# Water_Monitor_Interface_v7.net
KiCad netlist of a schematic drawn in EAGLE
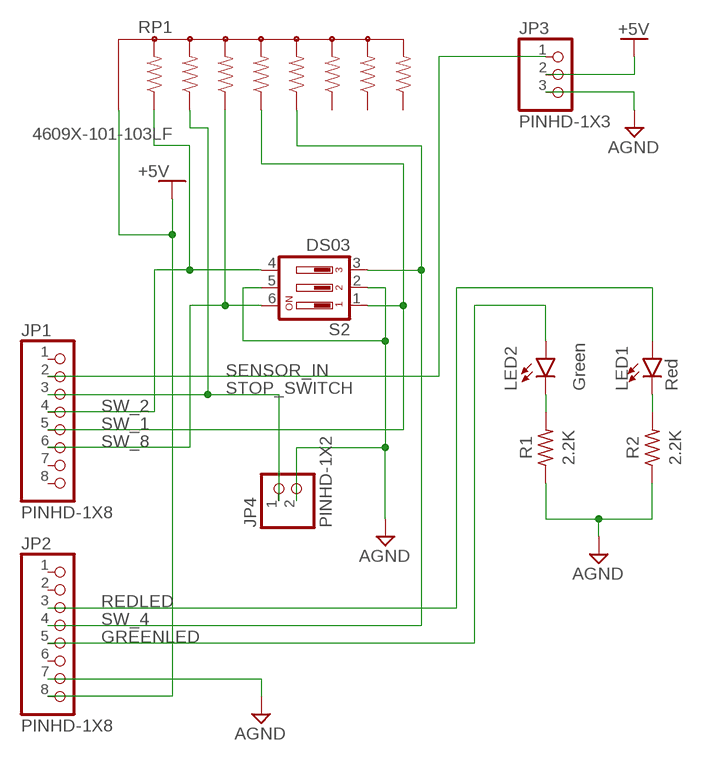
[diagram p0: schematic, sheet 1]

(export (version "E")
  (design (tool "Eeschema 10.0.6"))
  (components
    (comp (ref "JP1")
      (value "PINHD-1X8")
      (footprint "eagle-import:1X08")
      (libsource (lib "eagle-import") (part "PINHD-1X8"))
    )
    (comp (ref "JP2")
      (value "PINHD-1X8")
      (footprint "eagle-import:1X08")
      (libsource (lib "eagle-import") (part "PINHD-1X8"))
    )
    (comp (ref "JP3")
      (value "PINHD-1X3")
      (footprint "eagle-import:1X03")
      (libsource (lib "eagle-import") (part "PINHD-1X3"))
    )
    (comp (ref "JP4")
      (value "PINHD-1X2")
      (footprint "eagle-import:1X02")
      (libsource (lib "eagle-import") (part "PINHD-1X2"))
    )
    (comp (ref "LED1")
      (value "Red")
      (footprint "eagle-import:LED3MM")
      (libsource (lib "eagle-import") (part "led_259_LED3MM"))
    )
    (comp (ref "LED2")
      (value "Green")
      (footprint "eagle-import:LED_3MM-NS")
      (libsource (lib "eagle-import") (part "LED-3MM-NO_SILK"))
    )
    (comp (ref "R1")
      (value "2.2K")
      (footprint "eagle-import:RESAD724W46L381D178B")
      (libsource (lib "eagle-import") (part "R-USAXIAL-7.2MM-PITCH_"))
    )
    (comp (ref "R2")
      (value "2.2K")
      (footprint "eagle-import:RESAD724W46L381D178B")
      (libsource (lib "eagle-import") (part "R-USAXIAL-7.2MM-PITCH_"))
    )
    (comp (ref "RP1")
      (value "4609X-101-103LF")
      (footprint "eagle-import:4609X-101-103LF")
      (fields (field (name "MANUFACTURER") "Bourns Inc.") (field (name "CREATED_BY") "PCBLayout.com"))
      (libsource (lib "eagle-import") (part "4609X-101-103LF"))
    )
    (comp (ref "S2")
      (value "DS03")
      (footprint "eagle-import:DS-03")
      (fields (field (name "MPN") "MCNDS-03-V"))
      (libsource (lib "eagle-import") (part "DS03"))
    )
  )
  (nets
    (net (code "1") (name "+5V") (class "Default")
      (node (ref "JP2") (pin "8") (pinfunction "8_8") (pintype "passive"))
      (node (ref "JP3") (pin "2") (pinfunction "2_2") (pintype "passive"))
      (node (ref "RP1") (pin "1") (pinfunction "1_1") (pintype "passive"))
    )
    (net (code "2") (name "/GREENLED") (class "Default")
      (node (ref "JP2") (pin "5") (pinfunction "5_5") (pintype "passive"))
      (node (ref "LED2") (pin "A") (pinfunction "A_A") (pintype "passive"))
    )
    (net (code "3") (name "/REDLED") (class "Default")
      (node (ref "JP2") (pin "3") (pinfunction "3_3") (pintype "passive"))
      (node (ref "LED1") (pin "A") (pinfunction "A_A") (pintype "passive"))
    )
    (net (code "4") (name "/SENSOR_IN") (class "Default")
      (node (ref "JP1") (pin "2") (pinfunction "2_2") (pintype "passive"))
      (node (ref "JP3") (pin "1") (pinfunction "1_1") (pintype "passive"))
    )
    (net (code "5") (name "/STOP_SWITCH") (class "Default")
      (node (ref "JP1") (pin "3") (pinfunction "3_3") (pintype "passive"))
      (node (ref "JP4") (pin "1") (pinfunction "1_1") (pintype "passive"))
      (node (ref "RP1") (pin "3") (pinfunction "3_3") (pintype "passive"))
    )
    (net (code "6") (name "/SW_1") (class "Default")
      (node (ref "JP1") (pin "5") (pinfunction "5_5") (pintype "passive"))
      (node (ref "RP1") (pin "5") (pinfunction "5_5") (pintype "passive"))
      (node (ref "S2") (pin "1") (pinfunction "1_1") (pintype "passive"))
    )
    (net (code "7") (name "/SW_2") (class "Default")
      (node (ref "JP1") (pin "4") (pinfunction "4_4") (pintype "passive"))
      (node (ref "RP1") (pin "2") (pinfunction "2_2") (pintype "passive"))
      (node (ref "S2") (pin "4") (pinfunction "4_4") (pintype "passive"))
    )
    (net (code "8") (name "/SW_4") (class "Default")
      (node (ref "JP2") (pin "4") (pinfunction "4_4") (pintype "passive"))
      (node (ref "RP1") (pin "6") (pinfunction "6_6") (pintype "passive"))
      (node (ref "S2") (pin "3") (pinfunction "3_3") (pintype "passive"))
    )
    (net (code "9") (name "/SW_8") (class "Default")
      (node (ref "JP1") (pin "6") (pinfunction "6_6") (pintype "passive"))
      (node (ref "RP1") (pin "4") (pinfunction "4_4") (pintype "passive"))
      (node (ref "S2") (pin "6") (pinfunction "6_6") (pintype "passive"))
    )
    (net (code "10") (name "AGND") (class "Default")
      (node (ref "JP2") (pin "7") (pinfunction "7_7") (pintype "passive"))
      (node (ref "JP3") (pin "3") (pinfunction "3_3") (pintype "passive"))
      (node (ref "JP4") (pin "2") (pinfunction "2_2") (pintype "passive"))
      (node (ref "R1") (pin "1") (pinfunction "1_1") (pintype "passive"))
      (node (ref "R2") (pin "1") (pinfunction "1_1") (pintype "passive"))
      (node (ref "S2") (pin "2") (pinfunction "2_2") (pintype "passive"))
      (node (ref "S2") (pin "5") (pinfunction "5_5") (pintype "passive"))
    )
    (net (code "11") (name "Net-(LED1-C)") (class "Default")
      (node (ref "LED1") (pin "K") (pinfunction "C_K") (pintype "passive"))
      (node (ref "R2") (pin "2") (pinfunction "2_2") (pintype "passive"))
    )
    (net (code "12") (name "Net-(LED2-C)") (class "Default")
      (node (ref "LED2") (pin "K") (pinfunction "C_K") (pintype "passive"))
      (node (ref "R1") (pin "2") (pinfunction "2_2") (pintype "passive"))
    )
    (net (code "13") (name "unconnected-(JP1-Pad1)") (class "Default")
      (node (ref "JP1") (pin "1") (pinfunction "1_1") (pintype "passive"))
    )
    (net (code "14") (name "unconnected-(JP1-Pad7)") (class "Default")
      (node (ref "JP1") (pin "7") (pinfunction "7_7") (pintype "passive"))
    )
    (net (code "15") (name "unconnected-(JP1-Pad8)") (class "Default")
      (node (ref "JP1") (pin "8") (pinfunction "8_8") (pintype "passive"))
    )
    (net (code "16") (name "unconnected-(JP2-Pad1)") (class "Default")
      (node (ref "JP2") (pin "1") (pinfunction "1_1") (pintype "passive"))
    )
    (net (code "17") (name "unconnected-(JP2-Pad2)") (class "Default")
      (node (ref "JP2") (pin "2") (pinfunction "2_2") (pintype "passive"))
    )
    (net (code "18") (name "unconnected-(JP2-Pad6)") (class "Default")
      (node (ref "JP2") (pin "6") (pinfunction "6_6") (pintype "passive"))
    )
    (net (code "19") (name "unconnected-(RP1-Pad7)") (class "Default")
      (node (ref "RP1") (pin "7") (pinfunction "7_7") (pintype "passive"))
    )
    (net (code "20") (name "unconnected-(RP1-Pad8)") (class "Default")
      (node (ref "RP1") (pin "8") (pinfunction "8_8") (pintype "passive"))
    )
    (net (code "21") (name "unconnected-(RP1-Pad9)") (class "Default")
      (node (ref "RP1") (pin "9") (pinfunction "9_9") (pintype "passive"))
    )
  )
)
